# Half_Bridge_Driver.net
KiCad netlist of a schematic drawn in Altium Designer
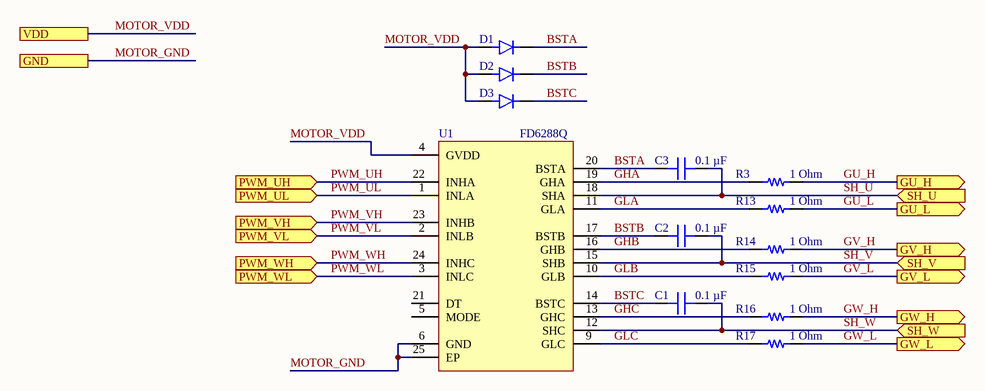
[diagram p0: Half_Bridge_Driver.SchDoc]

(export (version "E")
  (design (tool "Eeschema 10.0.6"))
  (components
    (comp (ref "C1")
      (value "0.1 µF")
      (footprint "CAP 0402_1005")
      (description "CAP CER 0.1UF 16V X7R 0402")
      (fields (field (name "PART NUMBER") "C0402C104K4RACAUTO") (field (name "MANUFACTURER") "KEMET"))
      (libsource (lib "Celestial Altium Library - altium_library") (part "Capacitor"))
    )
    (comp (ref "C2")
      (value "0.1 µF")
      (footprint "CAP 0402_1005")
      (description "CAP CER 0.1UF 16V X7R 0402")
      (fields (field (name "PART NUMBER") "C0402C104K4RACAUTO") (field (name "MANUFACTURER") "KEMET"))
      (libsource (lib "Celestial Altium Library - altium_library") (part "Capacitor"))
    )
    (comp (ref "C3")
      (value "0.1 µF")
      (footprint "CAP 0402_1005")
      (description "CAP CER 0.1UF 16V X7R 0402")
      (fields (field (name "PART NUMBER") "C0402C104K4RACAUTO") (field (name "MANUFACTURER") "KEMET"))
      (libsource (lib "Celestial Altium Library - altium_library") (part "Capacitor"))
    )
    (comp (ref "D1")
      (value "Diode")
      (footprint "Diode DFN1608D-2 (SOD1608)")
      (description "DFN1608D-2 (SOD1608)")
      (fields (field (name "MANUFACTURER") "Cree") (field (name "MOUSER PART NUMBER") "941-CLV1LFKBC7673673"))
      (libsource (lib "IC") (part "Diode"))
    )
    (comp (ref "D2")
      (value "Diode")
      (footprint "Diode DFN1608D-2 (SOD1608)")
      (description "DFN1608D-2 (SOD1608)")
      (fields (field (name "MANUFACTURER") "Cree") (field (name "MOUSER PART NUMBER") "941-CLV1LFKBC7673673"))
      (libsource (lib "IC") (part "Diode"))
    )
    (comp (ref "D3")
      (value "Diode")
      (footprint "Diode DFN1608D-2 (SOD1608)")
      (description "DFN1608D-2 (SOD1608)")
      (fields (field (name "MANUFACTURER") "Cree") (field (name "MOUSER PART NUMBER") "941-CLV1LFKBC7673673"))
      (libsource (lib "IC") (part "Diode"))
    )
    (comp (ref "R3")
      (value "1 Ohm")
      (footprint "RES 0402_1005")
      (description "RES 14.3K OHM 1% 1/10W 0402")
      (fields
        (field (name "PART NUMBER") "RK73H1ETTP1432F")
        (field (name "MANUFACTURER") "KOA Speer Electronics, Inc.")
      )
      (libsource (lib "Celestial Altium Library - altium_library") (part "Resistor"))
    )
    (comp (ref "R13")
      (value "1 Ohm")
      (footprint "RES 0402_1005")
      (description "RES 14.3K OHM 1% 1/10W 0402")
      (fields
        (field (name "PART NUMBER") "RK73H1ETTP1432F")
        (field (name "MANUFACTURER") "KOA Speer Electronics, Inc.")
      )
      (libsource (lib "Celestial Altium Library - altium_library") (part "Resistor"))
    )
    (comp (ref "R14")
      (value "1 Ohm")
      (footprint "RES 0402_1005")
      (description "RES 14.3K OHM 1% 1/10W 0402")
      (fields
        (field (name "PART NUMBER") "RK73H1ETTP1432F")
        (field (name "MANUFACTURER") "KOA Speer Electronics, Inc.")
      )
      (libsource (lib "Celestial Altium Library - altium_library") (part "Resistor"))
    )
    (comp (ref "R15")
      (value "1 Ohm")
      (footprint "RES 0402_1005")
      (description "RES 14.3K OHM 1% 1/10W 0402")
      (fields
        (field (name "PART NUMBER") "RK73H1ETTP1432F")
        (field (name "MANUFACTURER") "KOA Speer Electronics, Inc.")
      )
      (libsource (lib "Celestial Altium Library - altium_library") (part "Resistor"))
    )
    (comp (ref "R16")
      (value "1 Ohm")
      (footprint "RES 0402_1005")
      (description "RES 14.3K OHM 1% 1/10W 0402")
      (fields
        (field (name "PART NUMBER") "RK73H1ETTP1432F")
        (field (name "MANUFACTURER") "KOA Speer Electronics, Inc.")
      )
      (libsource (lib "Celestial Altium Library - altium_library") (part "Resistor"))
    )
    (comp (ref "R17")
      (value "1 Ohm")
      (footprint "RES 0402_1005")
      (description "RES 14.3K OHM 1% 1/10W 0402")
      (fields
        (field (name "PART NUMBER") "RK73H1ETTP1432F")
        (field (name "MANUFACTURER") "KOA Speer Electronics, Inc.")
      )
      (libsource (lib "Celestial Altium Library - altium_library") (part "Resistor"))
    )
    (comp (ref "U1")
      (value "FD6288Q")
      (footprint "QFN50P400X400X100-25N")
      (description "3 Phase Gate Driver 1.5-2.2A")
      (fields (field (name "MF") "Texas Instruments") (field (name "MP") "UCC27282DRCR"))
      (libsource (lib "IC") (part "FD6288Q"))
    )
  )
  (nets
    (net (code "1") (name "/BSTA") (class "Default")
      (node (ref "C3") (pin "1") (pinfunction "1_1") (pintype "passive"))
      (node (ref "D1") (pin "1") (pinfunction "A_1") (pintype "passive"))
      (node (ref "U1") (pin "20") (pinfunction "BSTA_20") (pintype "passive"))
    )
    (net (code "2") (name "/BSTB") (class "Default")
      (node (ref "C2") (pin "1") (pinfunction "1_1") (pintype "passive"))
      (node (ref "D2") (pin "1") (pinfunction "A_1") (pintype "passive"))
      (node (ref "U1") (pin "17") (pinfunction "BSTB_17") (pintype "passive"))
    )
    (net (code "3") (name "/BSTC") (class "Default")
      (node (ref "C1") (pin "1") (pinfunction "1_1") (pintype "passive"))
      (node (ref "D3") (pin "1") (pinfunction "A_1") (pintype "passive"))
      (node (ref "U1") (pin "14") (pinfunction "BSTC_14") (pintype "passive"))
    )
    (net (code "4") (name "/GHA") (class "Default")
      (node (ref "R3") (pin "1") (pinfunction "1_1") (pintype "passive"))
      (node (ref "U1") (pin "19") (pinfunction "GHA_19") (pintype "passive"))
    )
    (net (code "5") (name "/GHB") (class "Default")
      (node (ref "R14") (pin "1") (pinfunction "1_1") (pintype "passive"))
      (node (ref "U1") (pin "16") (pinfunction "GHB_16") (pintype "passive"))
    )
    (net (code "6") (name "/GHC") (class "Default")
      (node (ref "R16") (pin "1") (pinfunction "1_1") (pintype "passive"))
      (node (ref "U1") (pin "13") (pinfunction "GHC_13") (pintype "passive"))
    )
    (net (code "7") (name "/GLA") (class "Default")
      (node (ref "R13") (pin "1") (pinfunction "1_1") (pintype "passive"))
      (node (ref "U1") (pin "11") (pinfunction "GLA_11") (pintype "passive"))
    )
    (net (code "8") (name "/GLB") (class "Default")
      (node (ref "R15") (pin "1") (pinfunction "1_1") (pintype "passive"))
      (node (ref "U1") (pin "10") (pinfunction "GLB_10") (pintype "passive"))
    )
    (net (code "9") (name "/GLC") (class "Default")
      (node (ref "R17") (pin "1") (pinfunction "1_1") (pintype "passive"))
      (node (ref "U1") (pin "9") (pinfunction "GLC_9") (pintype "passive"))
    )
    (net (code "10") (name "/GU_H") (class "Default")
      (node (ref "R3") (pin "2") (pinfunction "2_2") (pintype "passive"))
    )
    (net (code "11") (name "/GU_L") (class "Default")
      (node (ref "R13") (pin "2") (pinfunction "2_2") (pintype "passive"))
    )
    (net (code "12") (name "/GV_H") (class "Default")
      (node (ref "R14") (pin "2") (pinfunction "2_2") (pintype "passive"))
    )
    (net (code "13") (name "/GV_L") (class "Default")
      (node (ref "R15") (pin "2") (pinfunction "2_2") (pintype "passive"))
    )
    (net (code "14") (name "/GW_H") (class "Default")
      (node (ref "R16") (pin "2") (pinfunction "2_2") (pintype "passive"))
    )
    (net (code "15") (name "/GW_L") (class "Default")
      (node (ref "R17") (pin "2") (pinfunction "2_2") (pintype "passive"))
    )
    (net (code "16") (name "/MOTOR_GND") (class "Default")
      (node (ref "U1") (pin "25") (pinfunction "EP_25") (pintype "passive"))
      (node (ref "U1") (pin "6") (pinfunction "GND_6") (pintype "passive"))
    )
    (net (code "17") (name "/MOTOR_VDD") (class "Default")
      (node (ref "D1") (pin "2") (pinfunction "BLUE(C)_2") (pintype "passive"))
      (node (ref "D2") (pin "2") (pinfunction "BLUE(C)_2") (pintype "passive"))
      (node (ref "D3") (pin "2") (pinfunction "BLUE(C)_2") (pintype "passive"))
      (node (ref "U1") (pin "4") (pinfunction "GVDD_4") (pintype "passive"))
    )
    (net (code "18") (name "/PWM_UH") (class "Default")
      (node (ref "U1") (pin "22") (pinfunction "INHA_22") (pintype "passive"))
    )
    (net (code "19") (name "/PWM_UL") (class "Default")
      (node (ref "U1") (pin "1") (pinfunction "INLA_1") (pintype "passive"))
    )
    (net (code "20") (name "/PWM_VH") (class "Default")
      (node (ref "U1") (pin "23") (pinfunction "INHB_23") (pintype "passive"))
    )
    (net (code "21") (name "/PWM_VL") (class "Default")
      (node (ref "U1") (pin "2") (pinfunction "INLB_2") (pintype "passive"))
    )
    (net (code "22") (name "/PWM_WH") (class "Default")
      (node (ref "U1") (pin "24") (pinfunction "INHC_24") (pintype "passive"))
    )
    (net (code "23") (name "/PWM_WL") (class "Default")
      (node (ref "U1") (pin "3") (pinfunction "INLC_3") (pintype "passive"))
    )
    (net (code "24") (name "/SH_U") (class "Default")
      (node (ref "C3") (pin "2") (pinfunction "2_2") (pintype "passive"))
      (node (ref "U1") (pin "18") (pinfunction "SHA_18") (pintype "passive"))
    )
    (net (code "25") (name "/SH_V") (class "Default")
      (node (ref "C2") (pin "2") (pinfunction "2_2") (pintype "passive"))
      (node (ref "U1") (pin "15") (pinfunction "SHB_15") (pintype "passive"))
    )
    (net (code "26") (name "/SH_W") (class "Default")
      (node (ref "C1") (pin "2") (pinfunction "2_2") (pintype "passive"))
      (node (ref "U1") (pin "12") (pinfunction "SHC_12") (pintype "passive"))
    )
    (net (code "27") (name "unconnected-(U1-DT-Pad21)") (class "Default")
      (node (ref "U1") (pin "21") (pinfunction "DT_21") (pintype "passive"))
    )
    (net (code "28") (name "unconnected-(U1-MODE-Pad5)") (class "Default")
      (node (ref "U1") (pin "5") (pinfunction "MODE_5") (pintype "passive"))
    )
  )
)
